# Teensy_Board.net
KiCad netlist of a schematic drawn in EAGLE
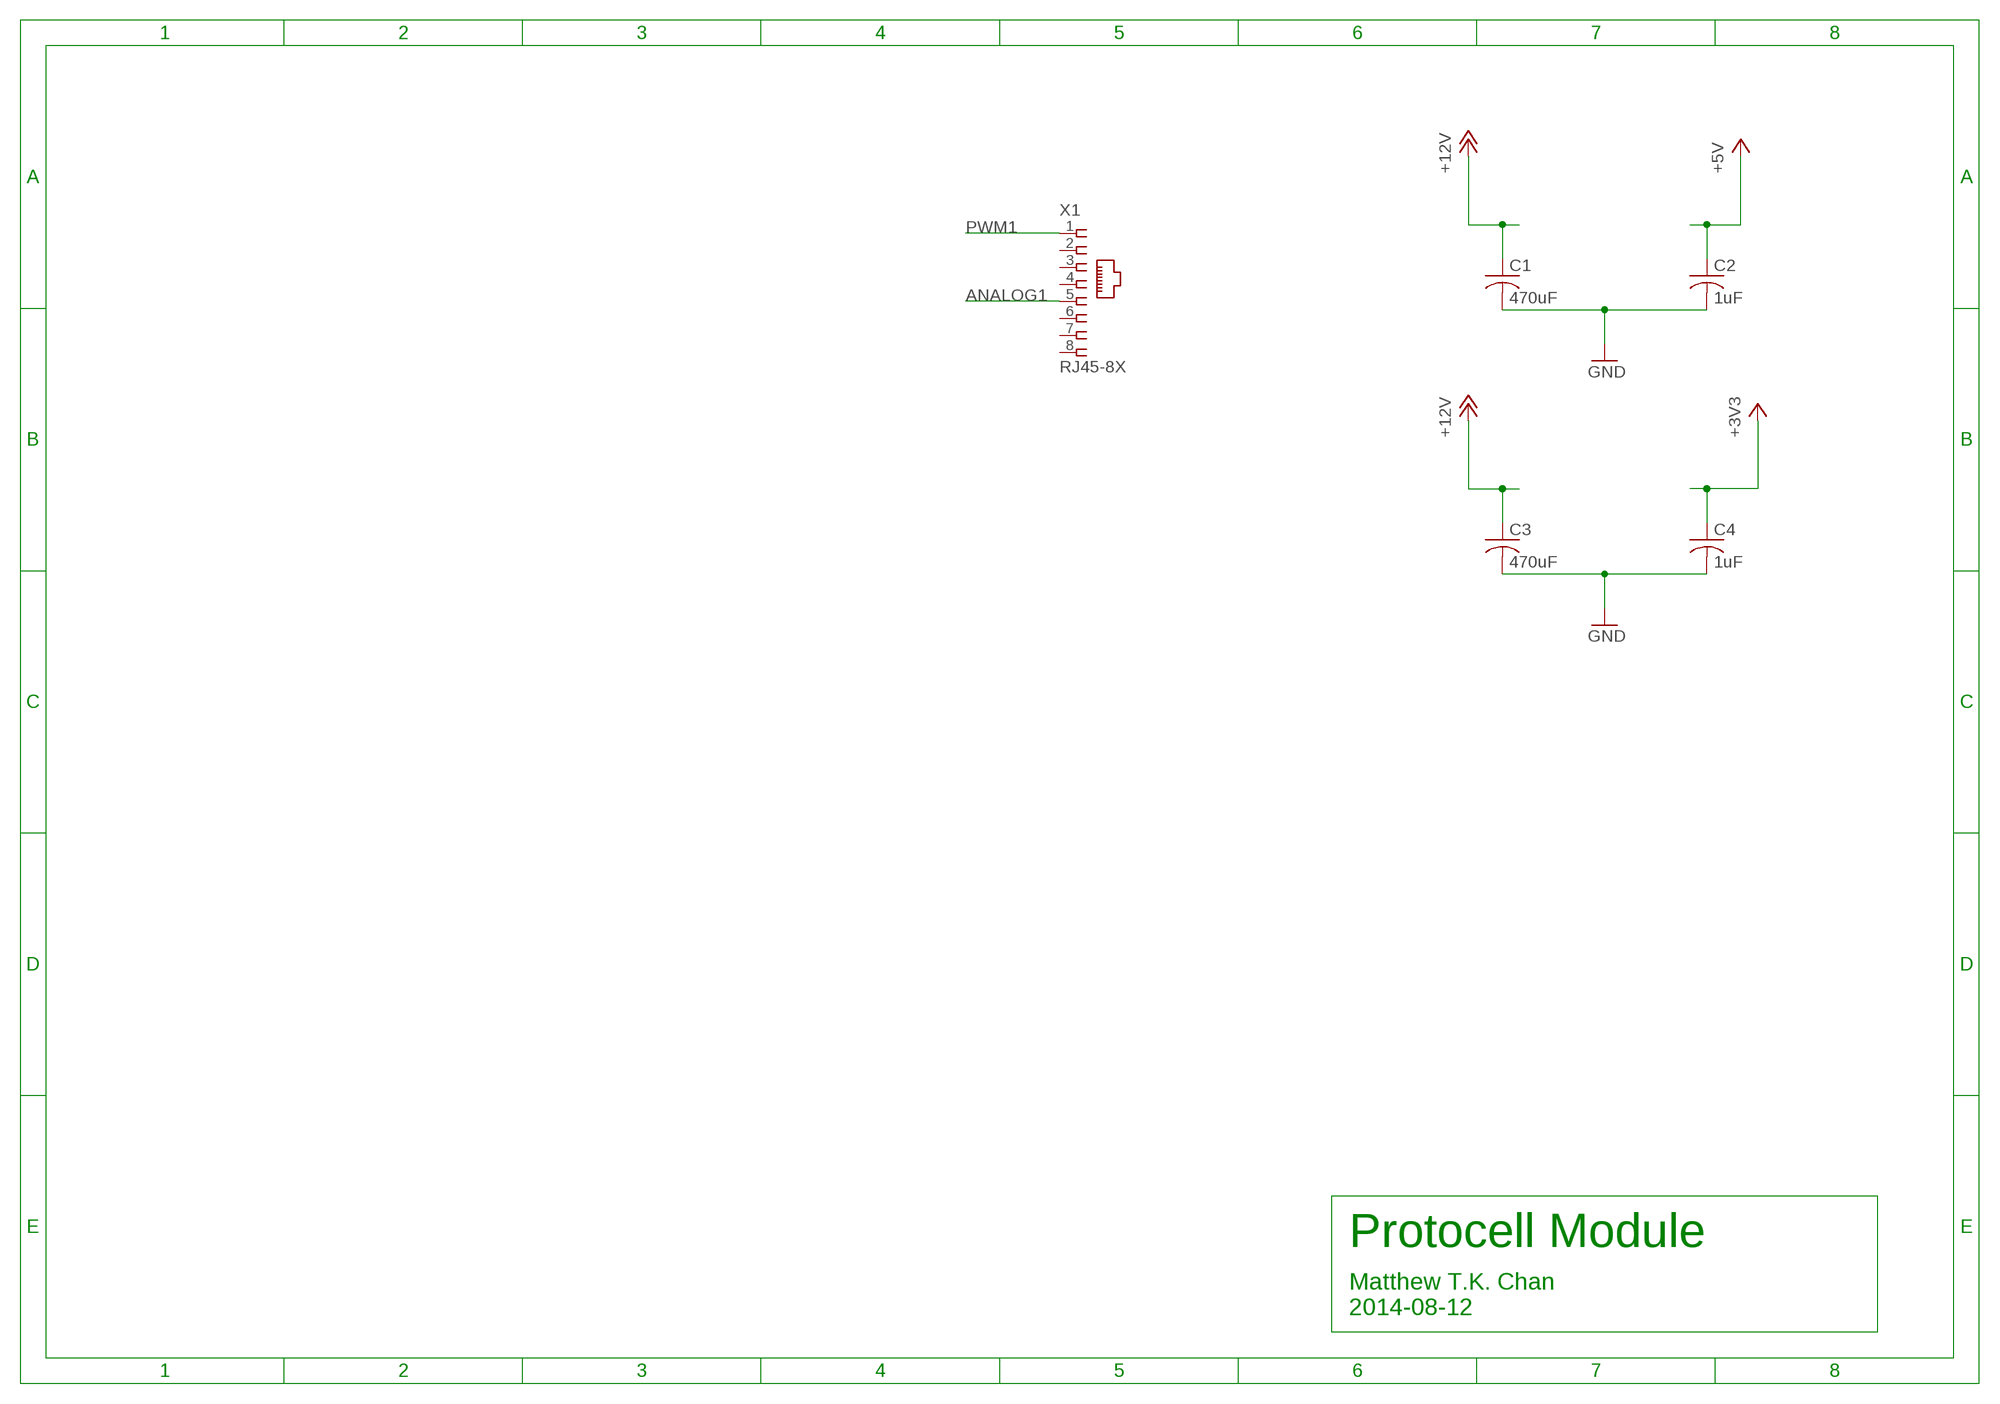
[diagram p0: schematic, sheet 1]

(export (version "E")
  (design (tool "Eeschema 10.0.6"))
  (components
    (comp (ref "C1")
      (value "470uF")
      (footprint "eagle-import:C0603")
      (libsource (lib "eagle-import") (part "C-USC0603"))
    )
    (comp (ref "C2")
      (value "1uF")
      (footprint "eagle-import:C0603")
      (libsource (lib "eagle-import") (part "C-USC0603"))
    )
    (comp (ref "C3")
      (value "470uF")
      (footprint "eagle-import:C0603")
      (libsource (lib "eagle-import") (part "C-USC0603"))
    )
    (comp (ref "C4")
      (value "1uF")
      (footprint "eagle-import:C0603")
      (libsource (lib "eagle-import") (part "C-USC0603"))
    )
    (comp (ref "X1")
      (value "RJ45-8X")
      (footprint "eagle-import:RJ45-NO-SHIELD")
      (libsource (lib "eagle-import") (part "RJ45-8X"))
    )
  )
  (nets
    (net (code "1") (name "+3V3") (class "Default")
      (node (ref "C4") (pin "1") (pinfunction "1_1") (pintype "passive"))
    )
    (net (code "2") (name "+5V") (class "Default")
      (node (ref "C2") (pin "1") (pinfunction "1_1") (pintype "passive"))
    )
    (net (code "3") (name "+12V") (class "Default")
      (node (ref "C1") (pin "1") (pinfunction "1_1") (pintype "passive"))
      (node (ref "C3") (pin "1") (pinfunction "1_1") (pintype "passive"))
    )
    (net (code "4") (name "/ANALOG1") (class "Default")
      (node (ref "X1") (pin "5") (pinfunction "5_5") (pintype "passive"))
    )
    (net (code "5") (name "/PWM1") (class "Default")
      (node (ref "X1") (pin "1") (pinfunction "1_1") (pintype "passive"))
    )
    (net (code "6") (name "GND") (class "Default")
      (node (ref "C1") (pin "2") (pinfunction "2_2") (pintype "passive"))
      (node (ref "C2") (pin "2") (pinfunction "2_2") (pintype "passive"))
      (node (ref "C3") (pin "2") (pinfunction "2_2") (pintype "passive"))
      (node (ref "C4") (pin "2") (pinfunction "2_2") (pintype "passive"))
    )
    (net (code "7") (name "unconnected-(X1-Pad2)") (class "Default")
      (node (ref "X1") (pin "2") (pinfunction "2_2") (pintype "passive"))
    )
    (net (code "8") (name "unconnected-(X1-Pad3)") (class "Default")
      (node (ref "X1") (pin "3") (pinfunction "3_3") (pintype "passive"))
    )
    (net (code "9") (name "unconnected-(X1-Pad4)") (class "Default")
      (node (ref "X1") (pin "4") (pinfunction "4_4") (pintype "passive"))
    )
    (net (code "10") (name "unconnected-(X1-Pad6)") (class "Default")
      (node (ref "X1") (pin "6") (pinfunction "6_6") (pintype "passive"))
    )
    (net (code "11") (name "unconnected-(X1-Pad7)") (class "Default")
      (node (ref "X1") (pin "7") (pinfunction "7_7") (pintype "passive"))
    )
    (net (code "12") (name "unconnected-(X1-Pad8)") (class "Default")
      (node (ref "X1") (pin "8") (pinfunction "8_8") (pintype "passive"))
    )
  )
)
